# ROV_PCB_PWR.net
KiCad netlist of a schematic drawn in Altium Designer
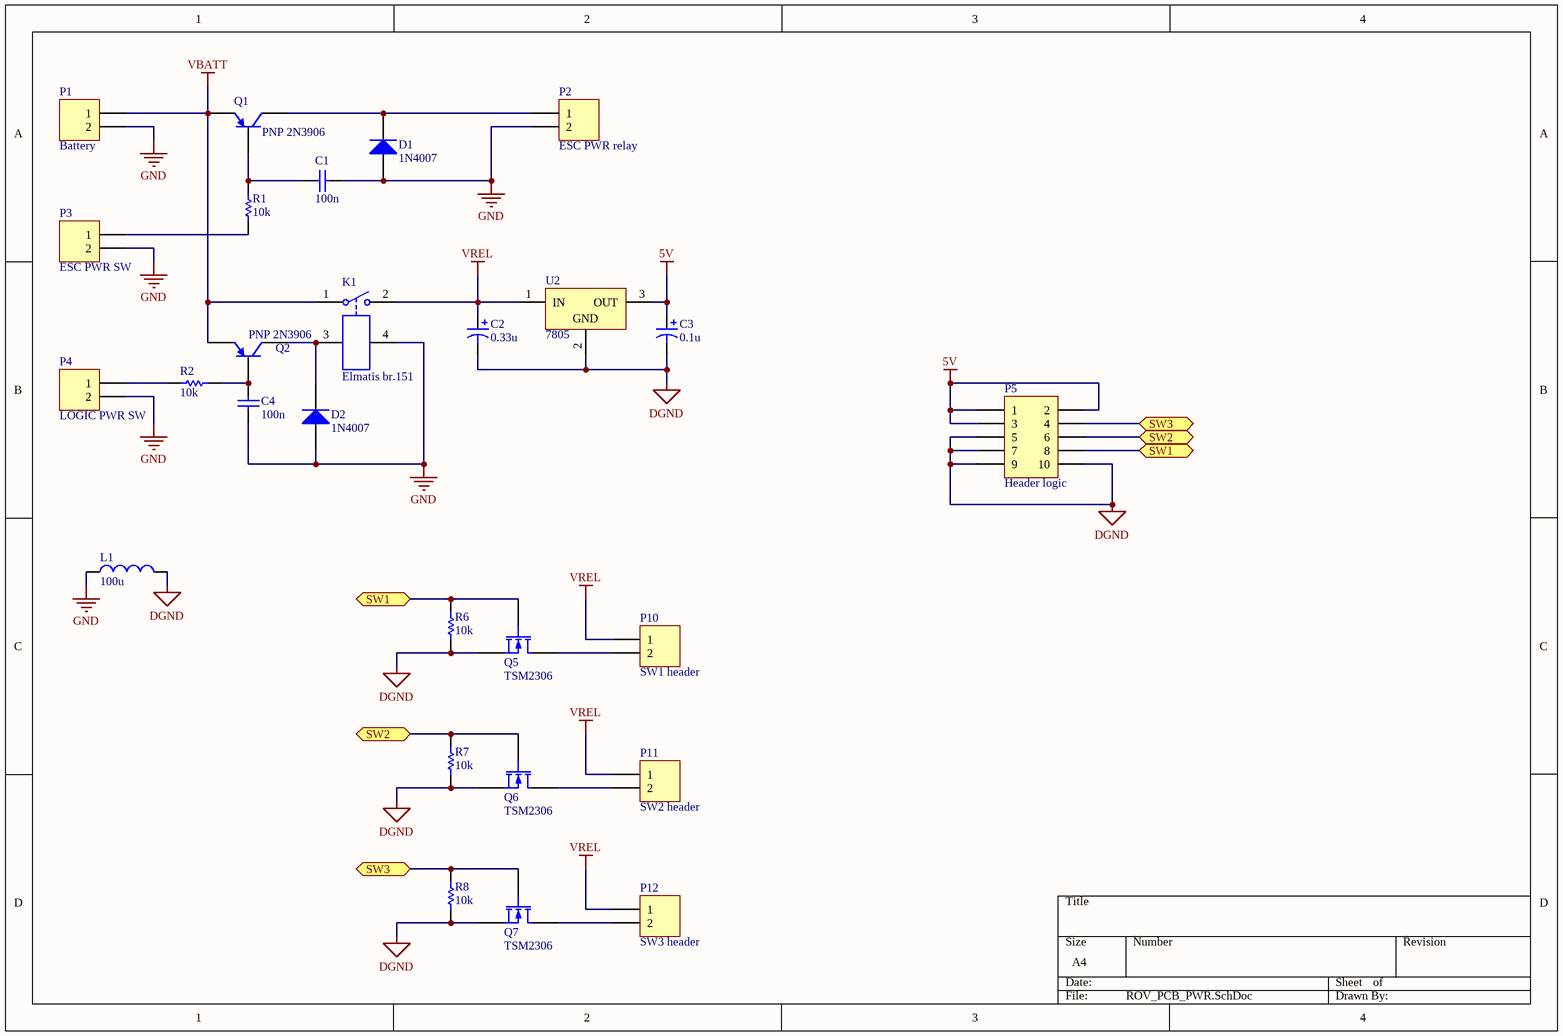
[diagram p0: ROV_PCB_PWR.SchDoc]

(export (version "E")
  (design (tool "Eeschema 10.0.6"))
  (components
    (comp (ref "C1")
      (value "100n")
      (footprint "RAD-0.1")
      (description "Capacitor")
      (fields (field (name "PUBLISHER") "Altium Limited"))
      (libsource (lib "Miscellaneous Devices") (part "Cap"))
    )
    (comp (ref "C2")
      (value "0.33u")
      (footprint "ELKO200")
      (description "Polarized Capacitor (Radial)")
      (fields (field (name "PART NUMBER") "C2006") (field (name "PUBLISHER") "Altium Limited"))
      (libsource (lib "Miscellaneous Devices") (part "Cap Pol1"))
    )
    (comp (ref "C3")
      (value "0.1u")
      (footprint "ELKO200")
      (description "Polarized Capacitor (Radial)")
      (fields (field (name "PART NUMBER") "ELKO100/ 35") (field (name "PUBLISHER") "Altium Limited"))
      (libsource (lib "Miscellaneous Devices") (part "Cap Pol1"))
    )
    (comp (ref "C4")
      (value "100n")
      (footprint "RAD-0.1")
      (description "Capacitor")
      (fields (field (name "PART NUMBER") "C5019") (field (name "PUBLISHER") "Altium Limited"))
      (libsource (lib "Miscellaneous Devices") (part "Cap"))
    )
    (comp (ref "D1")
      (value "1N4007")
      (footprint "DO-41")
      (description "1 Amp General Purpose Rectifier")
      (fields (field (name "PUBLISHER") "Altium Limited"))
      (libsource (lib "Miscellaneous Devices") (part "Diode 1N4007"))
    )
    (comp (ref "D2")
      (value "1N4007")
      (footprint "DO-41")
      (description "1 Amp General Purpose Rectifier")
      (fields (field (name "PUBLISHER") "Altium Limited"))
      (libsource (lib "Miscellaneous Devices") (part "Diode 1N4007"))
    )
    (comp (ref "K1")
      (value "Elmatis br.151")
      (footprint "REL151")
      (description "Single-Pole Single-Throw Relay")
      (fields (field (name "PART NUMBER") "151") (field (name "PUBLISHER") "Altium Limited"))
      (libsource (lib "Miscellaneous Devices") (part "Relay-SPST"))
    )
    (comp (ref "L1")
      (value "100u")
      (footprint "AXIAL-0.5")
      (description "Inductor")
      (fields (field (name "PART NUMBER") "BL016") (field (name "PUBLISHER") "Altium Limited"))
      (libsource (lib "Miscellaneous Devices") (part "Inductor"))
    )
    (comp (ref "P1")
      (value "Battery")
      (footprint "Klema")
      (description "Header, 2-Pin")
      (fields (field (name "PUBLISHER") "Altium Limited"))
      (libsource (lib "") (part "Header 2_1"))
    )
    (comp (ref "P2")
      (value "ESC PWR relay")
      (footprint "Klema")
      (description "Header, 2-Pin")
      (fields (field (name "PUBLISHER") "Altium Limited"))
      (libsource (lib "Miscellaneous Connectors") (part "Header 2"))
    )
    (comp (ref "P3")
      (value "ESC PWR SW")
      (footprint "HDR1X2")
      (description "Header, 2-Pin")
      (fields (field (name "PUBLISHER") "Altium Limited"))
      (libsource (lib "") (part "Header 2_1"))
    )
    (comp (ref "P4")
      (value "LOGIC PWR SW")
      (footprint "HDR1X2")
      (description "Header, 2-Pin")
      (fields (field (name "PUBLISHER") "Altium Limited"))
      (libsource (lib "") (part "Header 2_1"))
    )
    (comp (ref "P5")
      (value "Header logic")
      (footprint "HDR2X5")
      (description "Header, 5-Pin, Dual row")
      (fields (field (name "PUBLISHER") "Altium Limited"))
      (libsource (lib "Miscellaneous Connectors") (part "Header 5X2"))
    )
    (comp (ref "P10")
      (value "SW1 header")
      (footprint "Klema")
      (description "Header, 2-Pin")
      (fields (field (name "PUBLISHER") "Altium Limited"))
      (libsource (lib "Miscellaneous Connectors") (part "Header 2"))
    )
    (comp (ref "P11")
      (value "SW2 header")
      (footprint "Klema")
      (description "Header, 2-Pin")
      (fields (field (name "PUBLISHER") "Altium Limited"))
      (libsource (lib "Miscellaneous Connectors") (part "Header 2"))
    )
    (comp (ref "P12")
      (value "SW3 header")
      (footprint "Klema")
      (description "Header, 2-Pin")
      (fields (field (name "PUBLISHER") "Altium Limited"))
      (libsource (lib "Miscellaneous Connectors") (part "Header 2"))
    )
    (comp (ref "Q1")
      (value "PNP 2N3906")
      (footprint "MHDR1X3")
      (description "PNP Bipolar Transistor")
      (fields (field (name "PUBLISHER") "Altium Limited"))
      (libsource (lib "Miscellaneous Devices") (part "PNP"))
    )
    (comp (ref "Q2")
      (value "PNP 2N3906")
      (footprint "MHDR1X3")
      (description "PNP Bipolar Transistor")
      (fields (field (name "PUBLISHER") "Altium Limited"))
      (libsource (lib "Miscellaneous Devices") (part "PNP"))
    )
    (comp (ref "Q5")
      (value "TSM2306")
      (footprint "SOT-23_M")
      (fields (field (name "PUBLISHER") "Altium Limited"))
      (libsource (lib "Miscellaneous Devices") (part "MOSFET-N"))
    )
    (comp (ref "Q6")
      (value "TSM2306")
      (footprint "SOT-23_M")
      (fields (field (name "PUBLISHER") "Altium Limited"))
      (libsource (lib "Miscellaneous Devices") (part "MOSFET-N"))
    )
    (comp (ref "Q7")
      (value "TSM2306")
      (footprint "SOT-23_M")
      (fields (field (name "PUBLISHER") "Altium Limited"))
      (libsource (lib "Miscellaneous Devices") (part "MOSFET-N"))
    )
    (comp (ref "R1")
      (value "10k")
      (footprint "AXIAL-0.3")
      (description "Resistor")
      (fields (field (name "PUBLISHER") "Altium Limited"))
      (libsource (lib "Miscellaneous Devices") (part "Res1"))
    )
    (comp (ref "R2")
      (value "10k")
      (footprint "AXIAL-0.3")
      (description "Resistor")
      (fields (field (name "PUBLISHER") "Altium Limited"))
      (libsource (lib "Miscellaneous Devices") (part "Res1"))
    )
    (comp (ref "R6")
      (value "10k")
      (footprint "AXIAL-0.3")
      (description "Resistor")
      (fields (field (name "PUBLISHER") "Altium Limited"))
      (libsource (lib "Miscellaneous Devices") (part "Res1"))
    )
    (comp (ref "R7")
      (value "10k")
      (footprint "AXIAL-0.3")
      (description "Resistor")
      (fields (field (name "PUBLISHER") "Altium Limited"))
      (libsource (lib "Miscellaneous Devices") (part "Res1"))
    )
    (comp (ref "R8")
      (value "10k")
      (footprint "AXIAL-0.3")
      (description "Resistor")
      (fields (field (name "PUBLISHER") "Altium Limited"))
      (libsource (lib "Miscellaneous Devices") (part "Res1"))
    )
    (comp (ref "U2")
      (value "7805")
      (footprint "TO-220-AB")
      (description "Positive-Voltage Regulator")
      (fields (field (name "PUBLISHER") "Altium Limited"))
      (libsource (lib "TI Power Mgt Voltage Regulator") (part "µA7805CKC"))
    )
  )
  (nets
    (net (code "1") (name "/SW1") (class "Default")
      (node (ref "P5") (pin "8") (pinfunction "8_8") (pintype "passive"))
      (node (ref "Q5") (pin "1") (pinfunction "G_1") (pintype "passive"))
      (node (ref "R6") (pin "2") (pinfunction "2_2") (pintype "passive"))
    )
    (net (code "2") (name "/SW2") (class "Default")
      (node (ref "P5") (pin "6") (pinfunction "6_6") (pintype "passive"))
      (node (ref "Q6") (pin "1") (pinfunction "G_1") (pintype "passive"))
      (node (ref "R7") (pin "2") (pinfunction "2_2") (pintype "passive"))
    )
    (net (code "3") (name "/SW3") (class "Default")
      (node (ref "P5") (pin "4") (pinfunction "4_4") (pintype "passive"))
      (node (ref "Q7") (pin "1") (pinfunction "G_1") (pintype "passive"))
      (node (ref "R8") (pin "2") (pinfunction "2_2") (pintype "passive"))
    )
    (net (code "4") (name "5V") (class "Default")
      (node (ref "C3") (pin "1") (pinfunction "1_1") (pintype "passive"))
      (node (ref "P5") (pin "1") (pinfunction "1_1") (pintype "passive"))
      (node (ref "P5") (pin "2") (pinfunction "2_2") (pintype "passive"))
      (node (ref "P5") (pin "3") (pinfunction "3_3") (pintype "passive"))
      (node (ref "U2") (pin "3") (pinfunction "OUT_3") (pintype "power_in"))
    )
    (net (code "5") (name "DGND") (class "Default")
      (node (ref "C2") (pin "2") (pinfunction "2_2") (pintype "passive"))
      (node (ref "C3") (pin "2") (pinfunction "2_2") (pintype "passive"))
      (node (ref "L1") (pin "2") (pinfunction "2_2") (pintype "passive"))
      (node (ref "P5") (pin "10") (pinfunction "10_10") (pintype "passive"))
      (node (ref "P5") (pin "5") (pinfunction "5_5") (pintype "passive"))
      (node (ref "P5") (pin "7") (pinfunction "7_7") (pintype "passive"))
      (node (ref "P5") (pin "9") (pinfunction "9_9") (pintype "passive"))
      (node (ref "Q5") (pin "2") (pinfunction "S_2") (pintype "passive"))
      (node (ref "Q6") (pin "2") (pinfunction "S_2") (pintype "passive"))
      (node (ref "Q7") (pin "2") (pinfunction "S_2") (pintype "passive"))
      (node (ref "R6") (pin "1") (pinfunction "1_1") (pintype "passive"))
      (node (ref "R7") (pin "1") (pinfunction "1_1") (pintype "passive"))
      (node (ref "R8") (pin "1") (pinfunction "1_1") (pintype "passive"))
      (node (ref "U2") (pin "2") (pinfunction "GND_2") (pintype "power_in"))
    )
    (net (code "6") (name "GND") (class "Default")
      (node (ref "C1") (pin "1") (pinfunction "1_1") (pintype "passive"))
      (node (ref "C4") (pin "1") (pinfunction "1_1") (pintype "passive"))
      (node (ref "D1") (pin "1") (pinfunction "A_1") (pintype "passive"))
      (node (ref "D2") (pin "1") (pinfunction "A_1") (pintype "passive"))
      (node (ref "K1") (pin "4") (pinfunction "4_4") (pintype "passive"))
      (node (ref "L1") (pin "1") (pinfunction "1_1") (pintype "passive"))
      (node (ref "P1") (pin "2") (pinfunction "2_2") (pintype "passive"))
      (node (ref "P2") (pin "2") (pinfunction "2_2") (pintype "passive"))
      (node (ref "P3") (pin "2") (pinfunction "2_2") (pintype "passive"))
      (node (ref "P4") (pin "2") (pinfunction "2_2") (pintype "passive"))
    )
    (net (code "7") (name "Net-(D1-K)") (class "Default")
      (node (ref "D1") (pin "2") (pinfunction "K_2") (pintype "passive"))
      (node (ref "P2") (pin "1") (pinfunction "1_1") (pintype "passive"))
      (node (ref "Q1") (pin "3") (pinfunction "C_3") (pintype "passive"))
    )
    (net (code "8") (name "Net-(D2-K)") (class "Default")
      (node (ref "D2") (pin "2") (pinfunction "K_2") (pintype "passive"))
      (node (ref "K1") (pin "3") (pinfunction "3_3") (pintype "passive"))
      (node (ref "Q2") (pin "3") (pinfunction "C_3") (pintype "passive"))
    )
    (net (code "9") (name "Net-(P3-Pad1)") (class "Default")
      (node (ref "P3") (pin "1") (pinfunction "1_1") (pintype "passive"))
      (node (ref "R1") (pin "1") (pinfunction "1_1") (pintype "passive"))
    )
    (net (code "10") (name "Net-(P4-Pad1)") (class "Default")
      (node (ref "P4") (pin "1") (pinfunction "1_1") (pintype "passive"))
      (node (ref "R2") (pin "2") (pinfunction "2_2") (pintype "passive"))
    )
    (net (code "11") (name "Net-(Q1-B)") (class "Default")
      (node (ref "C1") (pin "2") (pinfunction "2_2") (pintype "passive"))
      (node (ref "Q1") (pin "2") (pinfunction "B_2") (pintype "passive"))
      (node (ref "R1") (pin "2") (pinfunction "2_2") (pintype "passive"))
    )
    (net (code "12") (name "Net-(Q2-B)") (class "Default")
      (node (ref "C4") (pin "2") (pinfunction "2_2") (pintype "passive"))
      (node (ref "Q2") (pin "2") (pinfunction "B_2") (pintype "passive"))
      (node (ref "R2") (pin "1") (pinfunction "1_1") (pintype "passive"))
    )
    (net (code "13") (name "Net-(Q5-D)") (class "Default")
      (node (ref "P10") (pin "2") (pinfunction "2_2") (pintype "passive"))
      (node (ref "Q5") (pin "3") (pinfunction "D_3") (pintype "passive"))
    )
    (net (code "14") (name "Net-(Q6-D)") (class "Default")
      (node (ref "P11") (pin "2") (pinfunction "2_2") (pintype "passive"))
      (node (ref "Q6") (pin "3") (pinfunction "D_3") (pintype "passive"))
    )
    (net (code "15") (name "Net-(Q7-D)") (class "Default")
      (node (ref "P12") (pin "2") (pinfunction "2_2") (pintype "passive"))
      (node (ref "Q7") (pin "3") (pinfunction "D_3") (pintype "passive"))
    )
    (net (code "16") (name "VBATT") (class "Default")
      (node (ref "K1") (pin "1") (pinfunction "1_1") (pintype "passive"))
      (node (ref "P1") (pin "1") (pinfunction "1_1") (pintype "passive"))
      (node (ref "Q1") (pin "1") (pinfunction "E_1") (pintype "passive"))
      (node (ref "Q2") (pin "1") (pinfunction "E_1") (pintype "passive"))
    )
    (net (code "17") (name "VREL") (class "Default")
      (node (ref "C2") (pin "1") (pinfunction "1_1") (pintype "passive"))
      (node (ref "K1") (pin "2") (pinfunction "2_2") (pintype "passive"))
      (node (ref "P10") (pin "1") (pinfunction "1_1") (pintype "passive"))
      (node (ref "P11") (pin "1") (pinfunction "1_1") (pintype "passive"))
      (node (ref "P12") (pin "1") (pinfunction "1_1") (pintype "passive"))
      (node (ref "U2") (pin "1") (pinfunction "IN_1") (pintype "power_in"))
    )
  )
)
